# MicroSDCard.net
KiCad netlist of a schematic drawn in Altium Designer
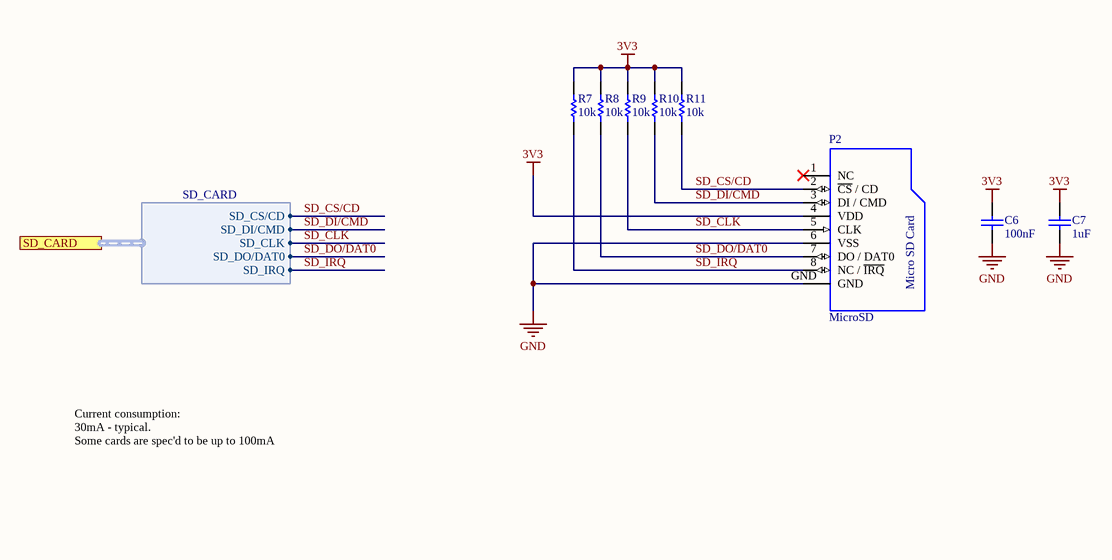
[diagram p0: MicroSDCard.SchDoc]

(export (version "E")
  (design (tool "Eeschema 10.0.6"))
  (components
    (comp (ref "C6")
      (value "100nF")
      (footprint "agh_racing_2018:CAP_0603_IPC_MD")
      (description "Capacitor")
      (fields (field (name "Comment") "Cap"))
      (libsource (lib "agh_racing_2018") (part "Cap"))
    )
    (comp (ref "C7")
      (value "1uF")
      (footprint "agh_racing_2018:CAP_0603_IPC_MD")
      (description "Capacitor")
      (fields (field (name "Comment") "Cap"))
      (libsource (lib "agh_racing_2018") (part "Cap"))
    )
    (comp (ref "P2")
      (value "MicroSD")
      (footprint "agh_racing_2018:MICROSDCARD_SOCKET")
      (description "Micro SD Card Connector")
      (libsource (lib "agh_racing_2018") (part "MicroSD"))
    )
    (comp (ref "R7")
      (value "10k")
      (footprint "agh_racing_2018:RES_0603_IPC_MD")
      (description "Resistor")
      (fields (field (name "Comment") "Res"))
      (libsource (lib "agh_racing_2018") (part "Res"))
    )
    (comp (ref "R8")
      (value "10k")
      (footprint "agh_racing_2018:RES_0603_IPC_MD")
      (description "Resistor")
      (fields (field (name "Comment") "Res"))
      (libsource (lib "agh_racing_2018") (part "Res"))
    )
    (comp (ref "R9")
      (value "10k")
      (footprint "agh_racing_2018:RES_0603_IPC_MD")
      (description "Resistor")
      (fields (field (name "Comment") "Res"))
      (libsource (lib "agh_racing_2018") (part "Res"))
    )
    (comp (ref "R10")
      (value "10k")
      (footprint "agh_racing_2018:RES_0603_IPC_MD")
      (description "Resistor")
      (fields (field (name "Comment") "Res"))
      (libsource (lib "agh_racing_2018") (part "Res"))
    )
    (comp (ref "R11")
      (value "10k")
      (footprint "agh_racing_2018:RES_0603_IPC_MD")
      (description "Resistor")
      (fields (field (name "Comment") "Res"))
      (libsource (lib "agh_racing_2018") (part "Res"))
    )
  )
  (nets
    (net (code "2") (name "/SD_CLK") (class "Default")
      (node (ref "P2") (pin "5") (pinfunction "CLK_5") (pintype "input"))
      (node (ref "R9") (pin "1") (pinfunction "1_1") (pintype "passive"))
    )
    (net (code "3") (name "/SD_CS{slash}CD") (class "Default")
      (node (ref "P2") (pin "2") (pinfunction "~{CS}_/_CD_2") (pintype "bidirectional"))
      (node (ref "R11") (pin "1") (pinfunction "1_1") (pintype "passive"))
    )
    (net (code "4") (name "/SD_DI{slash}CMD") (class "Default")
      (node (ref "P2") (pin "3") (pinfunction "DI_/_CMD_3") (pintype "bidirectional"))
      (node (ref "R10") (pin "1") (pinfunction "1_1") (pintype "passive"))
    )
    (net (code "5") (name "/SD_DO{slash}DAT0") (class "Default")
      (node (ref "P2") (pin "7") (pinfunction "DO_/_DAT0_7") (pintype "bidirectional"))
      (node (ref "R8") (pin "1") (pinfunction "1_1") (pintype "passive"))
    )
    (net (code "6") (name "/SD_IRQ") (class "Default")
      (node (ref "P2") (pin "8") (pinfunction "NC_/_~{IRQ}_8") (pintype "bidirectional"))
      (node (ref "R7") (pin "1") (pinfunction "1_1") (pintype "passive"))
    )
    (net (code "8") (name "3V3") (class "Default")
      (node (ref "C6") (pin "2") (pinfunction "2_2") (pintype "passive"))
      (node (ref "C7") (pin "2") (pinfunction "2_2") (pintype "passive"))
      (node (ref "P2") (pin "4") (pinfunction "VDD_4") (pintype "power_in"))
      (node (ref "R10") (pin "2") (pinfunction "2_2") (pintype "passive"))
      (node (ref "R11") (pin "2") (pinfunction "2_2") (pintype "passive"))
      (node (ref "R7") (pin "2") (pinfunction "2_2") (pintype "passive"))
      (node (ref "R8") (pin "2") (pinfunction "2_2") (pintype "passive"))
      (node (ref "R9") (pin "2") (pinfunction "2_2") (pintype "passive"))
    )
    (net (code "9") (name "GND") (class "Default")
      (node (ref "C6") (pin "1") (pinfunction "1_1") (pintype "passive"))
      (node (ref "C7") (pin "1") (pinfunction "1_1") (pintype "passive"))
      (node (ref "P2") (pin "6") (pinfunction "VSS_6") (pintype "power_in"))
      (node (ref "P2") (pin "GND") (pinfunction "GND_GND") (pintype "power_in"))
    )
    (net (code "10") (name "unconnected-(P2-NC-Pad1)") (class "Default")
      (node (ref "P2") (pin "1") (pinfunction "NC_1") (pintype "passive+no_connect"))
    )
  )
)
